# BoostSchDoc.net
KiCad netlist of a schematic drawn in Altium Designer
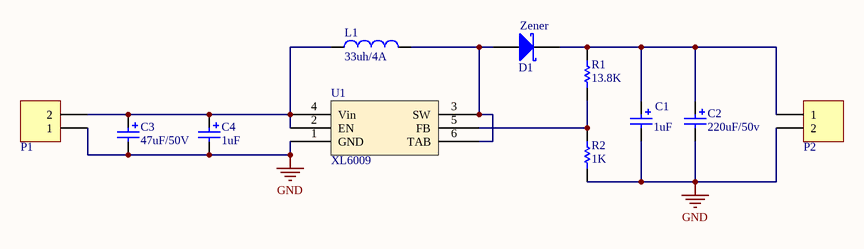
[diagram p0: BoostSchDoc.SchDoc]

(export (version "E")
  (design (tool "Eeschema 10.0.6"))
  (components
    (comp (ref "C1")
      (value "1uF")
      (footprint "CAP ALU SIZE B")
      (description "Polarized Capacitor (Radial)")
      (fields (field (name "Comment") "Cap Pol SMD"))
      (libsource (lib "PIF_Library") (part "Cap Pol SMD"))
    )
    (comp (ref "C2")
      (value "220uF/50v")
      (footprint "CAP ALU SIZE B")
      (description "Polarized Capacitor (Radial)")
      (fields (field (name "Comment") "Cap Pol SMD"))
      (libsource (lib "PIF_Library") (part "Cap Pol SMD"))
    )
    (comp (ref "C3")
      (value "47uF/50V")
      (footprint "CAP ALU SIZE B")
      (description "Polarized Capacitor (Radial)")
      (fields (field (name "Comment") "Cap Pol SMD"))
      (libsource (lib "PIF_Library") (part "Cap Pol SMD"))
    )
    (comp (ref "C4")
      (value "1uF")
      (footprint "CAP ALU SIZE B")
      (description "Polarized Capacitor (Radial)")
      (fields (field (name "Comment") "Cap Pol SMD"))
      (libsource (lib "PIF_Library") (part "Cap Pol SMD"))
    )
    (comp (ref "D1")
      (value "Zener")
      (footprint "SS34")
      (description "Schottky Diode")
      (fields (field (name "PUBLISHER") "Altium Limited"))
      (libsource (lib "PIF_Library") (part "D Schottky"))
    )
    (comp (ref "L1")
      (value "33uh/4A")
      (footprint "INDUCTOR 12.5x12.5")
      (description "Inductor")
      (libsource (lib "PIF_Library") (part "Inductor"))
    )
    (comp (ref "P1")
      (value "Domino 2")
      (footprint "DOMINO 2- 5mm")
      (description "Domino, 2-Pin")
      (fields (field (name "PUBLISHER") "Altium Limited"))
      (libsource (lib "PIF_Library") (part "Domino 2"))
    )
    (comp (ref "P2")
      (value "Domino 2")
      (footprint "DOMINO 2- 5mm")
      (description "Domino, 2-Pin")
      (fields (field (name "PUBLISHER") "Altium Limited"))
      (libsource (lib "") (part "Domino 2_1"))
    )
    (comp (ref "R1")
      (value "13.8K")
      (footprint "RES-SM-0603")
      (description "Resistor")
      (fields (field (name "Comment") "RESISTOR SMD"))
      (libsource (lib "PIF_Library") (part "RESISTOR SMD"))
    )
    (comp (ref "R2")
      (value "1K")
      (footprint "RES-SM-0603")
      (description "Resistor")
      (fields (field (name "Comment") "RESISTOR SMD"))
      (libsource (lib "PIF_Library") (part "RESISTOR SMD"))
    )
    (comp (ref "U1")
      (value "XL6009")
      (footprint "LM2596")
      (description "SMD")
      (libsource (lib "buck_boost") (part "XL6009"))
    )
  )
  (nets
    (net (code "1") (name "GND") (class "Default")
      (node (ref "C1") (pin "2") (pinfunction "2_2") (pintype "passive"))
      (node (ref "C2") (pin "2") (pinfunction "2_2") (pintype "passive"))
      (node (ref "C3") (pin "2") (pinfunction "2_2") (pintype "passive"))
      (node (ref "C4") (pin "2") (pinfunction "2_2") (pintype "passive"))
      (node (ref "P1") (pin "1") (pinfunction "1_1") (pintype "passive"))
      (node (ref "P2") (pin "2") (pinfunction "2_2") (pintype "passive"))
      (node (ref "R2") (pin "1") (pinfunction "1_1") (pintype "passive"))
      (node (ref "U1") (pin "1") (pinfunction "GND_1") (pintype "passive"))
    )
    (net (code "2") (name "Net-(D1-A)") (class "Default")
      (node (ref "D1") (pin "1") (pinfunction "A_1") (pintype "passive"))
      (node (ref "L1") (pin "2") (pinfunction "2_2") (pintype "passive"))
      (node (ref "U1") (pin "3") (pinfunction "SW_3") (pintype "passive"))
      (node (ref "U1") (pin "6") (pinfunction "TAB_6") (pintype "passive"))
    )
    (net (code "3") (name "Net-(D1-K)") (class "Default")
      (node (ref "C1") (pin "1") (pinfunction "1_1") (pintype "passive"))
      (node (ref "C2") (pin "1") (pinfunction "1_1") (pintype "passive"))
      (node (ref "D1") (pin "2") (pinfunction "K_2") (pintype "passive"))
      (node (ref "P2") (pin "1") (pinfunction "1_1") (pintype "passive"))
      (node (ref "R1") (pin "2") (pinfunction "2_2") (pintype "passive"))
    )
    (net (code "4") (name "Net-(U1-EN)") (class "Default")
      (node (ref "C3") (pin "1") (pinfunction "1_1") (pintype "passive"))
      (node (ref "C4") (pin "1") (pinfunction "1_1") (pintype "passive"))
      (node (ref "L1") (pin "1") (pinfunction "1_1") (pintype "passive"))
      (node (ref "P1") (pin "2") (pinfunction "2_2") (pintype "passive"))
      (node (ref "U1") (pin "2") (pinfunction "EN_2") (pintype "passive"))
      (node (ref "U1") (pin "4") (pinfunction "Vin_4") (pintype "passive"))
    )
    (net (code "5") (name "Net-(U1-FB)") (class "Default")
      (node (ref "R1") (pin "1") (pinfunction "1_1") (pintype "passive"))
      (node (ref "R2") (pin "2") (pinfunction "2_2") (pintype "passive"))
      (node (ref "U1") (pin "5") (pinfunction "FB_5") (pintype "passive"))
    )
  )
)
